# Sheet1.net
KiCad netlist of a schematic drawn in Altium Designer
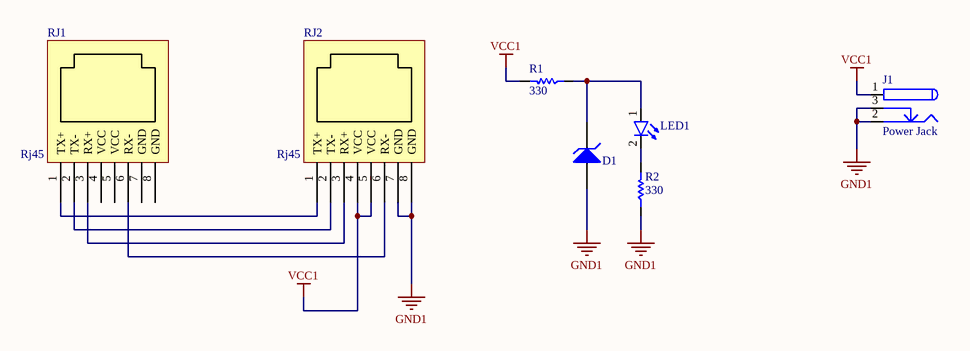
[diagram p0: Sheet1.SchDoc]

(export (version "E")
  (design (tool "Eeschema 10.0.6"))
  (components
    (comp (ref "D1")
      (value "Diode Zener")
      (footprint "Diode 1W")
      (description "Zener Diode")
      (fields (field (name "VOLTAGE") "3.3 V") (field (name "DESIGNER") "Saeid Jorablo"))
      (libsource (lib "Electrovolt Lib") (part "Diode Zener"))
    )
    (comp (ref "J1")
      (value "Power Jack")
      (footprint "Power Jack")
      (fields (field (name "DESIGNER") "Saeid Jorablo"))
      (libsource (lib "Electrovolt Lib") (part "Power Jack"))
    )
    (comp (ref "LED1")
      (value "Red")
      (footprint "LED-5mm")
      (description "LED")
      (fields (field (name "DESIGNER") "Saeid Jorablo"))
      (libsource (lib "Electrovolt Lib") (part "LED"))
    )
    (comp (ref "R1")
      (value "330")
      (footprint "RES 1206 (3216X08L)")
      (description "Resistor")
      (fields (field (name "TOLERANCE") "5%") (field (name "POWER") "1/8 W"))
      (libsource (lib "Electrovolt Lib") (part "Resistor"))
    )
    (comp (ref "R2")
      (value "330")
      (footprint "RES 1206 (3216X08L)")
      (description "Resistor")
      (fields (field (name "TOLERANCE") "5%") (field (name "POWER") "1/8 W"))
      (libsource (lib "Electrovolt Lib") (part "Resistor"))
    )
    (comp (ref "RJ1") (value "Rj45") (footprint "rj45-w57-1") (libsource (lib "Schlib1") (part "Rj45")))
    (comp (ref "RJ2") (value "Rj45") (footprint "rj45-w57-1") (libsource (lib "Schlib1") (part "Rj45")))
  )
  (nets
    (net (code "1") (name "GND1") (class "Default")
      (node (ref "D1") (pin "1") (pinfunction "A_1") (pintype "passive"))
      (node (ref "J1") (pin "2") (pinfunction "2_2") (pintype "power_in"))
      (node (ref "J1") (pin "3") (pinfunction "3_3") (pintype "power_in"))
      (node (ref "R2") (pin "1") (pinfunction "1_1") (pintype "passive"))
      (node (ref "RJ2") (pin "7") (pinfunction "GND_7") (pintype "passive"))
      (node (ref "RJ2") (pin "8") (pinfunction "GND_8") (pintype "passive"))
    )
    (net (code "2") (name "Net-(D1-K)") (class "Default")
      (node (ref "D1") (pin "2") (pinfunction "K_2") (pintype "passive"))
      (node (ref "LED1") (pin "1") (pinfunction "A_1") (pintype "passive"))
      (node (ref "R1") (pin "1") (pinfunction "1_1") (pintype "passive"))
    )
    (net (code "3") (name "Net-(LED1-K)") (class "Default")
      (node (ref "LED1") (pin "2") (pinfunction "K_2") (pintype "passive"))
      (node (ref "R2") (pin "2") (pinfunction "2_2") (pintype "passive"))
    )
    (net (code "4") (name "Net-(RJ1-RX+)") (class "Default")
      (node (ref "RJ1") (pin "3") (pinfunction "RX+_3") (pintype "passive"))
      (node (ref "RJ2") (pin "3") (pinfunction "RX+_3") (pintype "passive"))
    )
    (net (code "5") (name "Net-(RJ1-RX-)") (class "Default")
      (node (ref "RJ1") (pin "6") (pinfunction "RX-_6") (pintype "passive"))
      (node (ref "RJ2") (pin "6") (pinfunction "RX-_6") (pintype "passive"))
    )
    (net (code "6") (name "Net-(RJ1-TX+)") (class "Default")
      (node (ref "RJ1") (pin "1") (pinfunction "TX+_1") (pintype "passive"))
      (node (ref "RJ2") (pin "1") (pinfunction "TX+_1") (pintype "passive"))
    )
    (net (code "7") (name "Net-(RJ1-TX-)") (class "Default")
      (node (ref "RJ1") (pin "2") (pinfunction "TX-_2") (pintype "passive"))
      (node (ref "RJ2") (pin "2") (pinfunction "TX-_2") (pintype "passive"))
    )
    (net (code "8") (name "VCC1") (class "Default")
      (node (ref "J1") (pin "1") (pinfunction "1_1") (pintype "power_in"))
      (node (ref "R1") (pin "2") (pinfunction "2_2") (pintype "passive"))
      (node (ref "RJ2") (pin "4") (pinfunction "VCC_4") (pintype "passive"))
      (node (ref "RJ2") (pin "5") (pinfunction "VCC_5") (pintype "passive"))
    )
    (net (code "9") (name "unconnected-(RJ1-GND-Pad7)") (class "Default")
      (node (ref "RJ1") (pin "7") (pinfunction "GND_7") (pintype "passive"))
    )
    (net (code "10") (name "unconnected-(RJ1-GND-Pad8)") (class "Default")
      (node (ref "RJ1") (pin "8") (pinfunction "GND_8") (pintype "passive"))
    )
    (net (code "11") (name "unconnected-(RJ1-VCC-Pad4)") (class "Default")
      (node (ref "RJ1") (pin "4") (pinfunction "VCC_4") (pintype "passive"))
    )
    (net (code "12") (name "unconnected-(RJ1-VCC-Pad5)") (class "Default")
      (node (ref "RJ1") (pin "5") (pinfunction "VCC_5") (pintype "passive"))
    )
  )
)
